# IN-2_tubes.net
KiCad netlist of a schematic drawn in EAGLE
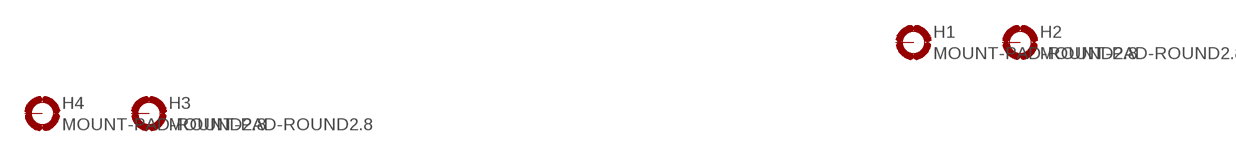
[diagram p0: schematic, sheet 1, part 1 of 2]
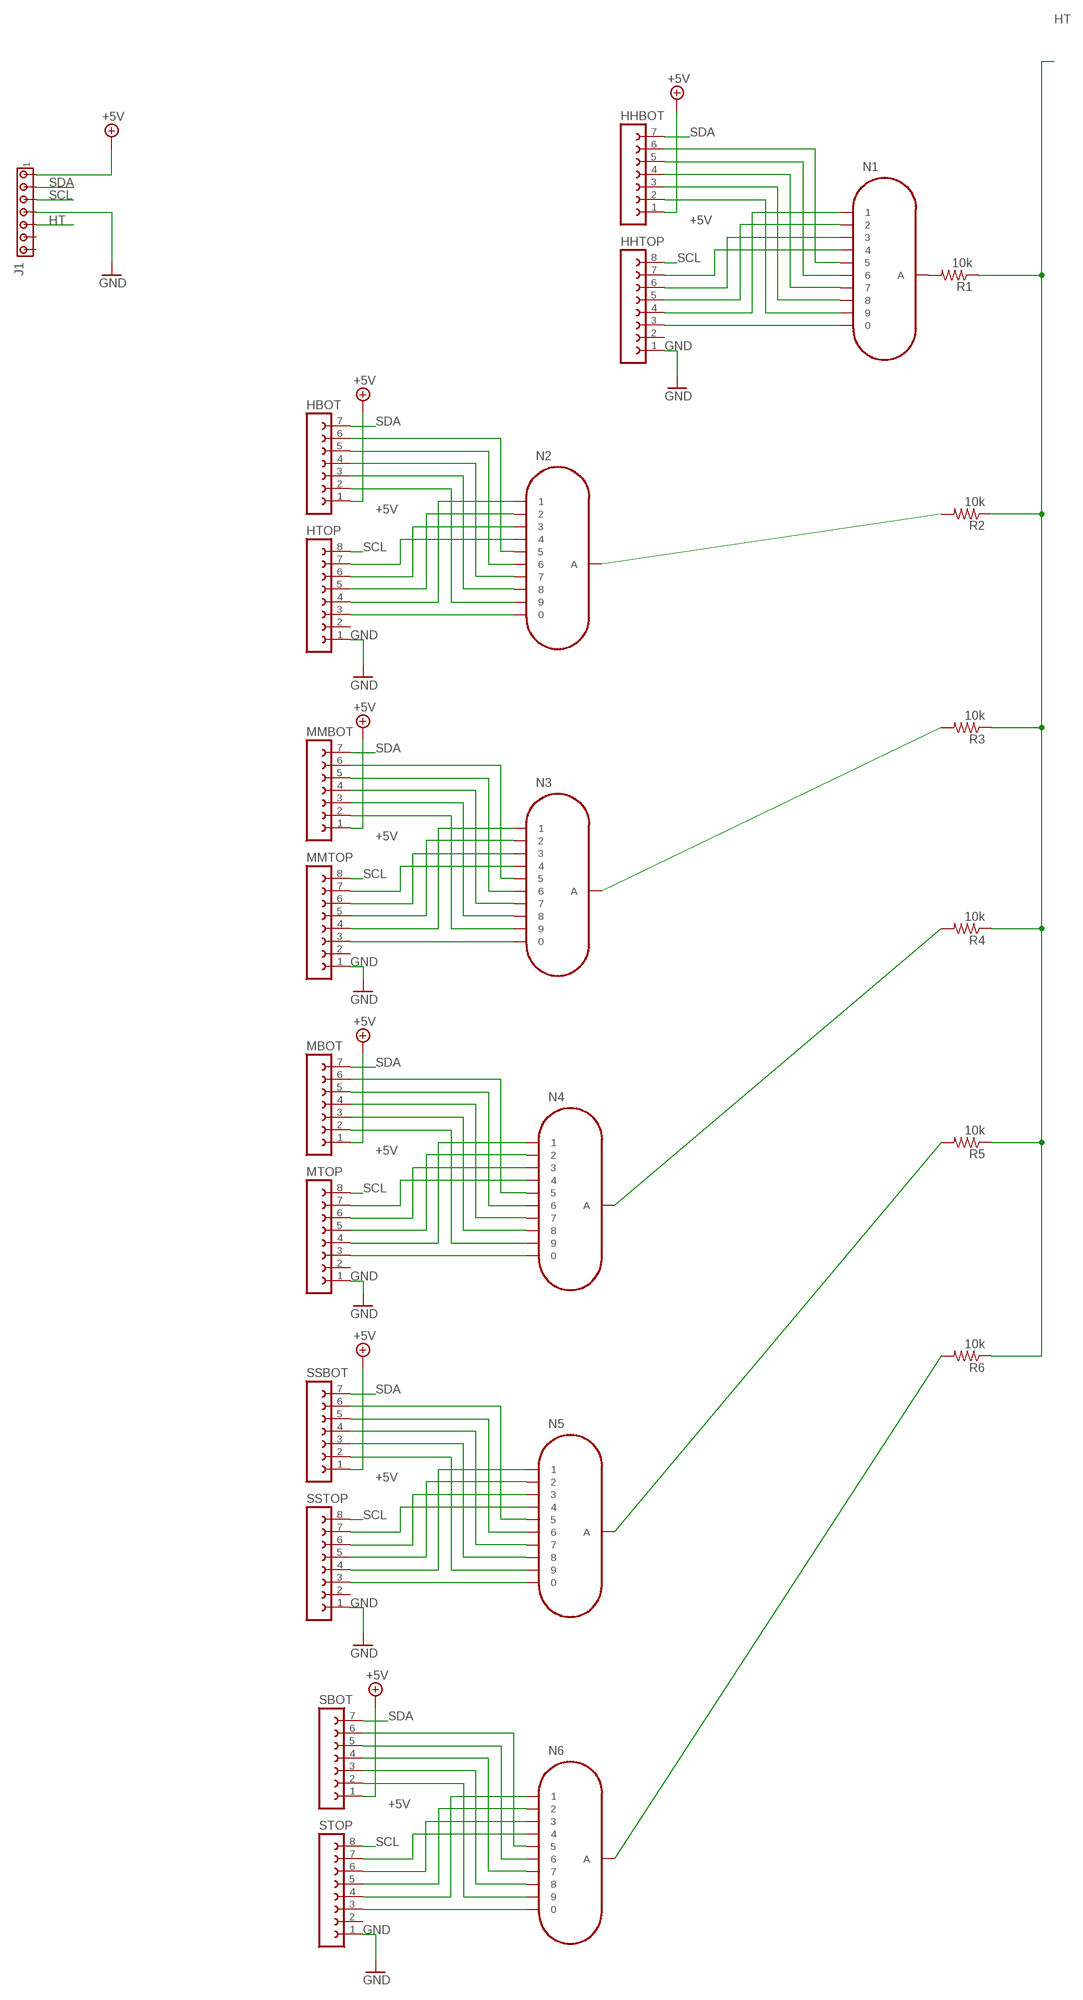
[diagram p1: schematic, sheet 1, part 2 of 2]

(export (version "E")
  (design (tool "Eeschema 10.0.6"))
  (components
    (comp (ref "H1")
      (value "MOUNT-PAD-ROUND2.8")
      (footprint "eagle-import:2,8-PAD")
      (libsource (lib "eagle-import") (part "MOUNT-PAD-ROUND2.8"))
    )
    (comp (ref "H2")
      (value "MOUNT-PAD-ROUND2.8")
      (footprint "eagle-import:2,8-PAD")
      (libsource (lib "eagle-import") (part "MOUNT-PAD-ROUND2.8"))
    )
    (comp (ref "H3")
      (value "MOUNT-PAD-ROUND2.8")
      (footprint "eagle-import:2,8-PAD")
      (libsource (lib "eagle-import") (part "MOUNT-PAD-ROUND2.8"))
    )
    (comp (ref "H4")
      (value "MOUNT-PAD-ROUND2.8")
      (footprint "eagle-import:2,8-PAD")
      (libsource (lib "eagle-import") (part "MOUNT-PAD-ROUND2.8"))
    )
    (comp (ref "HBOT")
      (value "FE07-1")
      (footprint "eagle-import:FE07")
      (libsource (lib "eagle-import") (part "FE07-1"))
    )
    (comp (ref "HHBOT")
      (value "FE07-1")
      (footprint "eagle-import:FE07")
      (libsource (lib "eagle-import") (part "FE07-1"))
    )
    (comp (ref "HHTOP")
      (value "FE08-1")
      (footprint "eagle-import:FE08")
      (libsource (lib "eagle-import") (part "FE08-1"))
    )
    (comp (ref "HTOP")
      (value "FE08-1")
      (footprint "eagle-import:FE08")
      (libsource (lib "eagle-import") (part "FE08-1"))
    )
    (comp (ref "J1")
      (value "MTA07-100")
      (footprint "eagle-import:10X07MTA")
      (libsource (lib "eagle-import") (part "MTA07-100"))
    )
    (comp (ref "MBOT")
      (value "FE07-1")
      (footprint "eagle-import:FE07")
      (libsource (lib "eagle-import") (part "FE07-1"))
    )
    (comp (ref "MMBOT")
      (value "FE07-1")
      (footprint "eagle-import:FE07")
      (libsource (lib "eagle-import") (part "FE07-1"))
    )
    (comp (ref "MMTOP")
      (value "FE08-1")
      (footprint "eagle-import:FE08")
      (libsource (lib "eagle-import") (part "FE08-1"))
    )
    (comp (ref "MTOP")
      (value "FE08-1")
      (footprint "eagle-import:FE08")
      (libsource (lib "eagle-import") (part "FE08-1"))
    )
    (comp (ref "N1")
      (value "IN-2")
      (footprint "eagle-import:IN-8")
      (libsource (lib "eagle-import") (part "IN-2"))
    )
    (comp (ref "N2")
      (value "IN-2")
      (footprint "eagle-import:IN-8")
      (libsource (lib "eagle-import") (part "IN-2"))
    )
    (comp (ref "N3")
      (value "IN-2")
      (footprint "eagle-import:IN-8")
      (libsource (lib "eagle-import") (part "IN-2"))
    )
    (comp (ref "N4")
      (value "IN-2")
      (footprint "eagle-import:IN-8")
      (libsource (lib "eagle-import") (part "IN-2"))
    )
    (comp (ref "N5")
      (value "IN-2")
      (footprint "eagle-import:IN-8")
      (libsource (lib "eagle-import") (part "IN-2"))
    )
    (comp (ref "N6")
      (value "IN-2")
      (footprint "eagle-import:IN-8")
      (libsource (lib "eagle-import") (part "IN-2"))
    )
    (comp (ref "R1")
      (value "10k")
      (footprint "eagle-import:M0805")
      (libsource (lib "eagle-import") (part "R-US_M0805"))
    )
    (comp (ref "R2")
      (value "10k")
      (footprint "eagle-import:M0805")
      (libsource (lib "eagle-import") (part "R-US_M0805"))
    )
    (comp (ref "R3")
      (value "10k")
      (footprint "eagle-import:M0805")
      (libsource (lib "eagle-import") (part "R-US_M0805"))
    )
    (comp (ref "R4")
      (value "10k")
      (footprint "eagle-import:M0805")
      (libsource (lib "eagle-import") (part "R-US_M0805"))
    )
    (comp (ref "R5")
      (value "10k")
      (footprint "eagle-import:M0805")
      (libsource (lib "eagle-import") (part "R-US_M0805"))
    )
    (comp (ref "R6")
      (value "10k")
      (footprint "eagle-import:M0805")
      (libsource (lib "eagle-import") (part "R-US_M0805"))
    )
    (comp (ref "SBOT")
      (value "FE07-1")
      (footprint "eagle-import:FE07")
      (libsource (lib "eagle-import") (part "FE07-1"))
    )
    (comp (ref "SSBOT")
      (value "FE07-1")
      (footprint "eagle-import:FE07")
      (libsource (lib "eagle-import") (part "FE07-1"))
    )
    (comp (ref "SSTOP")
      (value "FE08-1")
      (footprint "eagle-import:FE08")
      (libsource (lib "eagle-import") (part "FE08-1"))
    )
    (comp (ref "STOP")
      (value "FE08-1")
      (footprint "eagle-import:FE08")
      (libsource (lib "eagle-import") (part "FE08-1"))
    )
  )
  (nets
    (net (code "1") (name "+5V") (class "Default")
      (node (ref "HBOT") (pin "1") (pinfunction "1_1") (pintype "passive"))
      (node (ref "HHBOT") (pin "1") (pinfunction "1_1") (pintype "passive"))
      (node (ref "J1") (pin "1") (pinfunction "1_1") (pintype "passive"))
      (node (ref "MBOT") (pin "1") (pinfunction "1_1") (pintype "passive"))
      (node (ref "MMBOT") (pin "1") (pinfunction "1_1") (pintype "passive"))
      (node (ref "SBOT") (pin "1") (pinfunction "1_1") (pintype "passive"))
      (node (ref "SSBOT") (pin "1") (pinfunction "1_1") (pintype "passive"))
    )
    (net (code "2") (name "/HT") (class "Default")
      (node (ref "J1") (pin "5") (pinfunction "5_5") (pintype "passive"))
      (node (ref "R1") (pin "1") (pinfunction "1_1") (pintype "passive"))
      (node (ref "R2") (pin "1") (pinfunction "1_1") (pintype "passive"))
      (node (ref "R3") (pin "1") (pinfunction "1_1") (pintype "passive"))
      (node (ref "R4") (pin "1") (pinfunction "1_1") (pintype "passive"))
      (node (ref "R5") (pin "1") (pinfunction "1_1") (pintype "passive"))
      (node (ref "R6") (pin "1") (pinfunction "1_1") (pintype "passive"))
    )
    (net (code "3") (name "/SCL") (class "Default")
      (node (ref "HHTOP") (pin "8") (pinfunction "8_8") (pintype "passive"))
      (node (ref "HTOP") (pin "8") (pinfunction "8_8") (pintype "passive"))
      (node (ref "J1") (pin "3") (pinfunction "3_3") (pintype "passive"))
      (node (ref "MMTOP") (pin "8") (pinfunction "8_8") (pintype "passive"))
      (node (ref "MTOP") (pin "8") (pinfunction "8_8") (pintype "passive"))
      (node (ref "SSTOP") (pin "8") (pinfunction "8_8") (pintype "passive"))
      (node (ref "STOP") (pin "8") (pinfunction "8_8") (pintype "passive"))
    )
    (net (code "4") (name "/SDA") (class "Default")
      (node (ref "HBOT") (pin "7") (pinfunction "7_7") (pintype "passive"))
      (node (ref "HHBOT") (pin "7") (pinfunction "7_7") (pintype "passive"))
      (node (ref "J1") (pin "2") (pinfunction "2_2") (pintype "passive"))
      (node (ref "MBOT") (pin "7") (pinfunction "7_7") (pintype "passive"))
      (node (ref "MMBOT") (pin "7") (pinfunction "7_7") (pintype "passive"))
      (node (ref "SBOT") (pin "7") (pinfunction "7_7") (pintype "passive"))
      (node (ref "SSBOT") (pin "7") (pinfunction "7_7") (pintype "passive"))
    )
    (net (code "5") (name "GND") (class "Default")
      (node (ref "HHTOP") (pin "1") (pinfunction "1_1") (pintype "passive"))
      (node (ref "HTOP") (pin "1") (pinfunction "1_1") (pintype "passive"))
      (node (ref "J1") (pin "4") (pinfunction "4_4") (pintype "passive"))
      (node (ref "MMTOP") (pin "1") (pinfunction "1_1") (pintype "passive"))
      (node (ref "MTOP") (pin "1") (pinfunction "1_1") (pintype "passive"))
      (node (ref "SSTOP") (pin "1") (pinfunction "1_1") (pintype "passive"))
      (node (ref "STOP") (pin "1") (pinfunction "1_1") (pintype "passive"))
    )
    (net (code "6") (name "Net-(HBOT-Pad2)") (class "Default")
      (node (ref "HBOT") (pin "2") (pinfunction "2_2") (pintype "passive"))
      (node (ref "N2") (pin "9") (pinfunction "9_9") (pintype "bidirectional"))
    )
    (net (code "7") (name "Net-(HBOT-Pad3)") (class "Default")
      (node (ref "HBOT") (pin "3") (pinfunction "3_3") (pintype "passive"))
      (node (ref "N2") (pin "8") (pinfunction "8_8") (pintype "bidirectional"))
    )
    (net (code "8") (name "Net-(HBOT-Pad4)") (class "Default")
      (node (ref "HBOT") (pin "4") (pinfunction "4_4") (pintype "passive"))
      (node (ref "N2") (pin "7") (pinfunction "7_7") (pintype "bidirectional"))
    )
    (net (code "9") (name "Net-(HBOT-Pad5)") (class "Default")
      (node (ref "HBOT") (pin "5") (pinfunction "5_5") (pintype "passive"))
      (node (ref "N2") (pin "6") (pinfunction "6_6") (pintype "bidirectional"))
    )
    (net (code "10") (name "Net-(HBOT-Pad6)") (class "Default")
      (node (ref "HBOT") (pin "6") (pinfunction "6_6") (pintype "passive"))
      (node (ref "N2") (pin "5") (pinfunction "5_5") (pintype "bidirectional"))
    )
    (net (code "11") (name "Net-(HHBOT-Pad2)") (class "Default")
      (node (ref "HHBOT") (pin "2") (pinfunction "2_2") (pintype "passive"))
      (node (ref "N1") (pin "9") (pinfunction "9_9") (pintype "bidirectional"))
    )
    (net (code "12") (name "Net-(HHBOT-Pad3)") (class "Default")
      (node (ref "HHBOT") (pin "3") (pinfunction "3_3") (pintype "passive"))
      (node (ref "N1") (pin "8") (pinfunction "8_8") (pintype "bidirectional"))
    )
    (net (code "13") (name "Net-(HHBOT-Pad4)") (class "Default")
      (node (ref "HHBOT") (pin "4") (pinfunction "4_4") (pintype "passive"))
      (node (ref "N1") (pin "7") (pinfunction "7_7") (pintype "bidirectional"))
    )
    (net (code "14") (name "Net-(HHBOT-Pad5)") (class "Default")
      (node (ref "HHBOT") (pin "5") (pinfunction "5_5") (pintype "passive"))
      (node (ref "N1") (pin "6") (pinfunction "6_6") (pintype "bidirectional"))
    )
    (net (code "15") (name "Net-(HHBOT-Pad6)") (class "Default")
      (node (ref "HHBOT") (pin "6") (pinfunction "6_6") (pintype "passive"))
      (node (ref "N1") (pin "5") (pinfunction "5_5") (pintype "bidirectional"))
    )
    (net (code "16") (name "Net-(HHTOP-Pad3)") (class "Default")
      (node (ref "HHTOP") (pin "3") (pinfunction "3_3") (pintype "passive"))
      (node (ref "N1") (pin "0") (pinfunction "0_0") (pintype "bidirectional"))
    )
    (net (code "17") (name "Net-(HHTOP-Pad4)") (class "Default")
      (node (ref "HHTOP") (pin "4") (pinfunction "4_4") (pintype "passive"))
      (node (ref "N1") (pin "1") (pinfunction "1_1") (pintype "bidirectional"))
    )
    (net (code "18") (name "Net-(HHTOP-Pad5)") (class "Default")
      (node (ref "HHTOP") (pin "5") (pinfunction "5_5") (pintype "passive"))
      (node (ref "N1") (pin "2") (pinfunction "2_2") (pintype "bidirectional"))
    )
    (net (code "19") (name "Net-(HHTOP-Pad6)") (class "Default")
      (node (ref "HHTOP") (pin "6") (pinfunction "6_6") (pintype "passive"))
      (node (ref "N1") (pin "3") (pinfunction "3_3") (pintype "bidirectional"))
    )
    (net (code "20") (name "Net-(HHTOP-Pad7)") (class "Default")
      (node (ref "HHTOP") (pin "7") (pinfunction "7_7") (pintype "passive"))
      (node (ref "N1") (pin "4") (pinfunction "4_4") (pintype "bidirectional"))
    )
    (net (code "21") (name "Net-(HTOP-Pad3)") (class "Default")
      (node (ref "HTOP") (pin "3") (pinfunction "3_3") (pintype "passive"))
      (node (ref "N2") (pin "0") (pinfunction "0_0") (pintype "bidirectional"))
    )
    (net (code "22") (name "Net-(HTOP-Pad4)") (class "Default")
      (node (ref "HTOP") (pin "4") (pinfunction "4_4") (pintype "passive"))
      (node (ref "N2") (pin "1") (pinfunction "1_1") (pintype "bidirectional"))
    )
    (net (code "23") (name "Net-(HTOP-Pad5)") (class "Default")
      (node (ref "HTOP") (pin "5") (pinfunction "5_5") (pintype "passive"))
      (node (ref "N2") (pin "2") (pinfunction "2_2") (pintype "bidirectional"))
    )
    (net (code "24") (name "Net-(HTOP-Pad6)") (class "Default")
      (node (ref "HTOP") (pin "6") (pinfunction "6_6") (pintype "passive"))
      (node (ref "N2") (pin "3") (pinfunction "3_3") (pintype "bidirectional"))
    )
    (net (code "25") (name "Net-(HTOP-Pad7)") (class "Default")
      (node (ref "HTOP") (pin "7") (pinfunction "7_7") (pintype "passive"))
      (node (ref "N2") (pin "4") (pinfunction "4_4") (pintype "bidirectional"))
    )
    (net (code "26") (name "Net-(MBOT-Pad2)") (class "Default")
      (node (ref "MBOT") (pin "2") (pinfunction "2_2") (pintype "passive"))
      (node (ref "N4") (pin "9") (pinfunction "9_9") (pintype "bidirectional"))
    )
    (net (code "27") (name "Net-(MBOT-Pad3)") (class "Default")
      (node (ref "MBOT") (pin "3") (pinfunction "3_3") (pintype "passive"))
      (node (ref "N4") (pin "8") (pinfunction "8_8") (pintype "bidirectional"))
    )
    (net (code "28") (name "Net-(MBOT-Pad4)") (class "Default")
      (node (ref "MBOT") (pin "4") (pinfunction "4_4") (pintype "passive"))
      (node (ref "N4") (pin "7") (pinfunction "7_7") (pintype "bidirectional"))
    )
    (net (code "29") (name "Net-(MBOT-Pad5)") (class "Default")
      (node (ref "MBOT") (pin "5") (pinfunction "5_5") (pintype "passive"))
      (node (ref "N4") (pin "6") (pinfunction "6_6") (pintype "bidirectional"))
    )
    (net (code "30") (name "Net-(MBOT-Pad6)") (class "Default")
      (node (ref "MBOT") (pin "6") (pinfunction "6_6") (pintype "passive"))
      (node (ref "N4") (pin "5") (pinfunction "5_5") (pintype "bidirectional"))
    )
    (net (code "31") (name "Net-(MMBOT-Pad2)") (class "Default")
      (node (ref "MMBOT") (pin "2") (pinfunction "2_2") (pintype "passive"))
      (node (ref "N3") (pin "9") (pinfunction "9_9") (pintype "bidirectional"))
    )
    (net (code "32") (name "Net-(MMBOT-Pad3)") (class "Default")
      (node (ref "MMBOT") (pin "3") (pinfunction "3_3") (pintype "passive"))
      (node (ref "N3") (pin "8") (pinfunction "8_8") (pintype "bidirectional"))
    )
    (net (code "33") (name "Net-(MMBOT-Pad4)") (class "Default")
      (node (ref "MMBOT") (pin "4") (pinfunction "4_4") (pintype "passive"))
      (node (ref "N3") (pin "7") (pinfunction "7_7") (pintype "bidirectional"))
    )
    (net (code "34") (name "Net-(MMBOT-Pad5)") (class "Default")
      (node (ref "MMBOT") (pin "5") (pinfunction "5_5") (pintype "passive"))
      (node (ref "N3") (pin "6") (pinfunction "6_6") (pintype "bidirectional"))
    )
    (net (code "35") (name "Net-(MMBOT-Pad6)") (class "Default")
      (node (ref "MMBOT") (pin "6") (pinfunction "6_6") (pintype "passive"))
      (node (ref "N3") (pin "5") (pinfunction "5_5") (pintype "bidirectional"))
    )
    (net (code "36") (name "Net-(MMTOP-Pad3)") (class "Default")
      (node (ref "MMTOP") (pin "3") (pinfunction "3_3") (pintype "passive"))
      (node (ref "N3") (pin "0") (pinfunction "0_0") (pintype "bidirectional"))
    )
    (net (code "37") (name "Net-(MMTOP-Pad4)") (class "Default")
      (node (ref "MMTOP") (pin "4") (pinfunction "4_4") (pintype "passive"))
      (node (ref "N3") (pin "1") (pinfunction "1_1") (pintype "bidirectional"))
    )
    (net (code "38") (name "Net-(MMTOP-Pad5)") (class "Default")
      (node (ref "MMTOP") (pin "5") (pinfunction "5_5") (pintype "passive"))
      (node (ref "N3") (pin "2") (pinfunction "2_2") (pintype "bidirectional"))
    )
    (net (code "39") (name "Net-(MMTOP-Pad6)") (class "Default")
      (node (ref "MMTOP") (pin "6") (pinfunction "6_6") (pintype "passive"))
      (node (ref "N3") (pin "3") (pinfunction "3_3") (pintype "bidirectional"))
    )
    (net (code "40") (name "Net-(MMTOP-Pad7)") (class "Default")
      (node (ref "MMTOP") (pin "7") (pinfunction "7_7") (pintype "passive"))
      (node (ref "N3") (pin "4") (pinfunction "4_4") (pintype "bidirectional"))
    )
    (net (code "41") (name "Net-(MTOP-Pad3)") (class "Default")
      (node (ref "MTOP") (pin "3") (pinfunction "3_3") (pintype "passive"))
      (node (ref "N4") (pin "0") (pinfunction "0_0") (pintype "bidirectional"))
    )
    (net (code "42") (name "Net-(MTOP-Pad4)") (class "Default")
      (node (ref "MTOP") (pin "4") (pinfunction "4_4") (pintype "passive"))
      (node (ref "N4") (pin "1") (pinfunction "1_1") (pintype "bidirectional"))
    )
    (net (code "43") (name "Net-(MTOP-Pad5)") (class "Default")
      (node (ref "MTOP") (pin "5") (pinfunction "5_5") (pintype "passive"))
      (node (ref "N4") (pin "2") (pinfunction "2_2") (pintype "bidirectional"))
    )
    (net (code "44") (name "Net-(MTOP-Pad6)") (class "Default")
      (node (ref "MTOP") (pin "6") (pinfunction "6_6") (pintype "passive"))
      (node (ref "N4") (pin "3") (pinfunction "3_3") (pintype "bidirectional"))
    )
    (net (code "45") (name "Net-(MTOP-Pad7)") (class "Default")
      (node (ref "MTOP") (pin "7") (pinfunction "7_7") (pintype "passive"))
      (node (ref "N4") (pin "4") (pinfunction "4_4") (pintype "bidirectional"))
    )
    (net (code "46") (name "Net-(N1-PadA)") (class "Default")
      (node (ref "N1") (pin "A") (pinfunction "A_A") (pintype "bidirectional"))
      (node (ref "R1") (pin "2") (pinfunction "2_2") (pintype "passive"))
    )
    (net (code "47") (name "Net-(N2-PadA)") (class "Default")
      (node (ref "N2") (pin "A") (pinfunction "A_A") (pintype "bidirectional"))
      (node (ref "R2") (pin "2") (pinfunction "2_2") (pintype "passive"))
    )
    (net (code "48") (name "Net-(N3-PadA)") (class "Default")
      (node (ref "N3") (pin "A") (pinfunction "A_A") (pintype "bidirectional"))
      (node (ref "R3") (pin "2") (pinfunction "2_2") (pintype "passive"))
    )
    (net (code "49") (name "Net-(N4-PadA)") (class "Default")
      (node (ref "N4") (pin "A") (pinfunction "A_A") (pintype "bidirectional"))
      (node (ref "R4") (pin "2") (pinfunction "2_2") (pintype "passive"))
    )
    (net (code "50") (name "Net-(N5-Pad0)") (class "Default")
      (node (ref "N5") (pin "0") (pinfunction "0_0") (pintype "bidirectional"))
      (node (ref "SSTOP") (pin "3") (pinfunction "3_3") (pintype "passive"))
    )
    (net (code "51") (name "Net-(N5-Pad1)") (class "Default")
      (node (ref "N5") (pin "1") (pinfunction "1_1") (pintype "bidirectional"))
      (node (ref "SSTOP") (pin "4") (pinfunction "4_4") (pintype "passive"))
    )
    (net (code "52") (name "Net-(N5-Pad2)") (class "Default")
      (node (ref "N5") (pin "2") (pinfunction "2_2") (pintype "bidirectional"))
      (node (ref "SSTOP") (pin "5") (pinfunction "5_5") (pintype "passive"))
    )
    (net (code "53") (name "Net-(N5-Pad3)") (class "Default")
      (node (ref "N5") (pin "3") (pinfunction "3_3") (pintype "bidirectional"))
      (node (ref "SSTOP") (pin "6") (pinfunction "6_6") (pintype "passive"))
    )
    (net (code "54") (name "Net-(N5-Pad4)") (class "Default")
      (node (ref "N5") (pin "4") (pinfunction "4_4") (pintype "bidirectional"))
      (node (ref "SSTOP") (pin "7") (pinfunction "7_7") (pintype "passive"))
    )
    (net (code "55") (name "Net-(N5-Pad5)") (class "Default")
      (node (ref "N5") (pin "5") (pinfunction "5_5") (pintype "bidirectional"))
      (node (ref "SSBOT") (pin "6") (pinfunction "6_6") (pintype "passive"))
    )
    (net (code "56") (name "Net-(N5-Pad6)") (class "Default")
      (node (ref "N5") (pin "6") (pinfunction "6_6") (pintype "bidirectional"))
      (node (ref "SSBOT") (pin "5") (pinfunction "5_5") (pintype "passive"))
    )
    (net (code "57") (name "Net-(N5-Pad7)") (class "Default")
      (node (ref "N5") (pin "7") (pinfunction "7_7") (pintype "bidirectional"))
      (node (ref "SSBOT") (pin "4") (pinfunction "4_4") (pintype "passive"))
    )
    (net (code "58") (name "Net-(N5-Pad8)") (class "Default")
      (node (ref "N5") (pin "8") (pinfunction "8_8") (pintype "bidirectional"))
      (node (ref "SSBOT") (pin "3") (pinfunction "3_3") (pintype "passive"))
    )
    (net (code "59") (name "Net-(N5-Pad9)") (class "Default")
      (node (ref "N5") (pin "9") (pinfunction "9_9") (pintype "bidirectional"))
      (node (ref "SSBOT") (pin "2") (pinfunction "2_2") (pintype "passive"))
    )
    (net (code "60") (name "Net-(N5-PadA)") (class "Default")
      (node (ref "N5") (pin "A") (pinfunction "A_A") (pintype "bidirectional"))
      (node (ref "R5") (pin "2") (pinfunction "2_2") (pintype "passive"))
    )
    (net (code "61") (name "Net-(N6-Pad0)") (class "Default")
      (node (ref "N6") (pin "0") (pinfunction "0_0") (pintype "bidirectional"))
      (node (ref "STOP") (pin "3") (pinfunction "3_3") (pintype "passive"))
    )
    (net (code "62") (name "Net-(N6-Pad1)") (class "Default")
      (node (ref "N6") (pin "1") (pinfunction "1_1") (pintype "bidirectional"))
      (node (ref "STOP") (pin "4") (pinfunction "4_4") (pintype "passive"))
    )
    (net (code "63") (name "Net-(N6-Pad2)") (class "Default")
      (node (ref "N6") (pin "2") (pinfunction "2_2") (pintype "bidirectional"))
      (node (ref "STOP") (pin "5") (pinfunction "5_5") (pintype "passive"))
    )
    (net (code "64") (name "Net-(N6-Pad3)") (class "Default")
      (node (ref "N6") (pin "3") (pinfunction "3_3") (pintype "bidirectional"))
      (node (ref "STOP") (pin "6") (pinfunction "6_6") (pintype "passive"))
    )
    (net (code "65") (name "Net-(N6-Pad4)") (class "Default")
      (node (ref "N6") (pin "4") (pinfunction "4_4") (pintype "bidirectional"))
      (node (ref "STOP") (pin "7") (pinfunction "7_7") (pintype "passive"))
    )
    (net (code "66") (name "Net-(N6-Pad5)") (class "Default")
      (node (ref "N6") (pin "5") (pinfunction "5_5") (pintype "bidirectional"))
      (node (ref "SBOT") (pin "6") (pinfunction "6_6") (pintype "passive"))
    )
    (net (code "67") (name "Net-(N6-Pad6)") (class "Default")
      (node (ref "N6") (pin "6") (pinfunction "6_6") (pintype "bidirectional"))
      (node (ref "SBOT") (pin "5") (pinfunction "5_5") (pintype "passive"))
    )
    (net (code "68") (name "Net-(N6-Pad7)") (class "Default")
      (node (ref "N6") (pin "7") (pinfunction "7_7") (pintype "bidirectional"))
      (node (ref "SBOT") (pin "4") (pinfunction "4_4") (pintype "passive"))
    )
    (net (code "69") (name "Net-(N6-Pad8)") (class "Default")
      (node (ref "N6") (pin "8") (pinfunction "8_8") (pintype "bidirectional"))
      (node (ref "SBOT") (pin "3") (pinfunction "3_3") (pintype "passive"))
    )
    (net (code "70") (name "Net-(N6-Pad9)") (class "Default")
      (node (ref "N6") (pin "9") (pinfunction "9_9") (pintype "bidirectional"))
      (node (ref "SBOT") (pin "2") (pinfunction "2_2") (pintype "passive"))
    )
    (net (code "71") (name "Net-(N6-PadA)") (class "Default")
      (node (ref "N6") (pin "A") (pinfunction "A_A") (pintype "bidirectional"))
      (node (ref "R6") (pin "2") (pinfunction "2_2") (pintype "passive"))
    )
    (net (code "72") (name "unconnected-(H1-MOUNT-PadB2,8)") (class "Default")
      (node (ref "H1") (pin "B2,8") (pinfunction "MOUNT_B2,8") (pintype "passive"))
    )
    (net (code "73") (name "unconnected-(H2-MOUNT-PadB2,8)") (class "Default")
      (node (ref "H2") (pin "B2,8") (pinfunction "MOUNT_B2,8") (pintype "passive"))
    )
    (net (code "74") (name "unconnected-(H3-MOUNT-PadB2,8)") (class "Default")
      (node (ref "H3") (pin "B2,8") (pinfunction "MOUNT_B2,8") (pintype "passive"))
    )
    (net (code "75") (name "unconnected-(H4-MOUNT-PadB2,8)") (class "Default")
      (node (ref "H4") (pin "B2,8") (pinfunction "MOUNT_B2,8") (pintype "passive"))
    )
    (net (code "76") (name "unconnected-(HHTOP-Pad2)") (class "Default")
      (node (ref "HHTOP") (pin "2") (pinfunction "2_2") (pintype "passive"))
    )
    (net (code "77") (name "unconnected-(HTOP-Pad2)") (class "Default")
      (node (ref "HTOP") (pin "2") (pinfunction "2_2") (pintype "passive"))
    )
    (net (code "78") (name "unconnected-(J1-Pad6)") (class "Default")
      (node (ref "J1") (pin "6") (pinfunction "6_6") (pintype "passive"))
    )
    (net (code "79") (name "unconnected-(J1-Pad7)") (class "Default")
      (node (ref "J1") (pin "7") (pinfunction "7_7") (pintype "passive"))
    )
    (net (code "80") (name "unconnected-(MMTOP-Pad2)") (class "Default")
      (node (ref "MMTOP") (pin "2") (pinfunction "2_2") (pintype "passive"))
    )
    (net (code "81") (name "unconnected-(MTOP-Pad2)") (class "Default")
      (node (ref "MTOP") (pin "2") (pinfunction "2_2") (pintype "passive"))
    )
    (net (code "82") (name "unconnected-(SSTOP-Pad2)") (class "Default")
      (node (ref "SSTOP") (pin "2") (pinfunction "2_2") (pintype "passive"))
    )
    (net (code "83") (name "unconnected-(STOP-Pad2)") (class "Default")
      (node (ref "STOP") (pin "2") (pinfunction "2_2") (pintype "passive"))
    )
  )
)
